# p07_cpu_renesas_144.net
KiCad netlist of a schematic drawn in Altium Designer
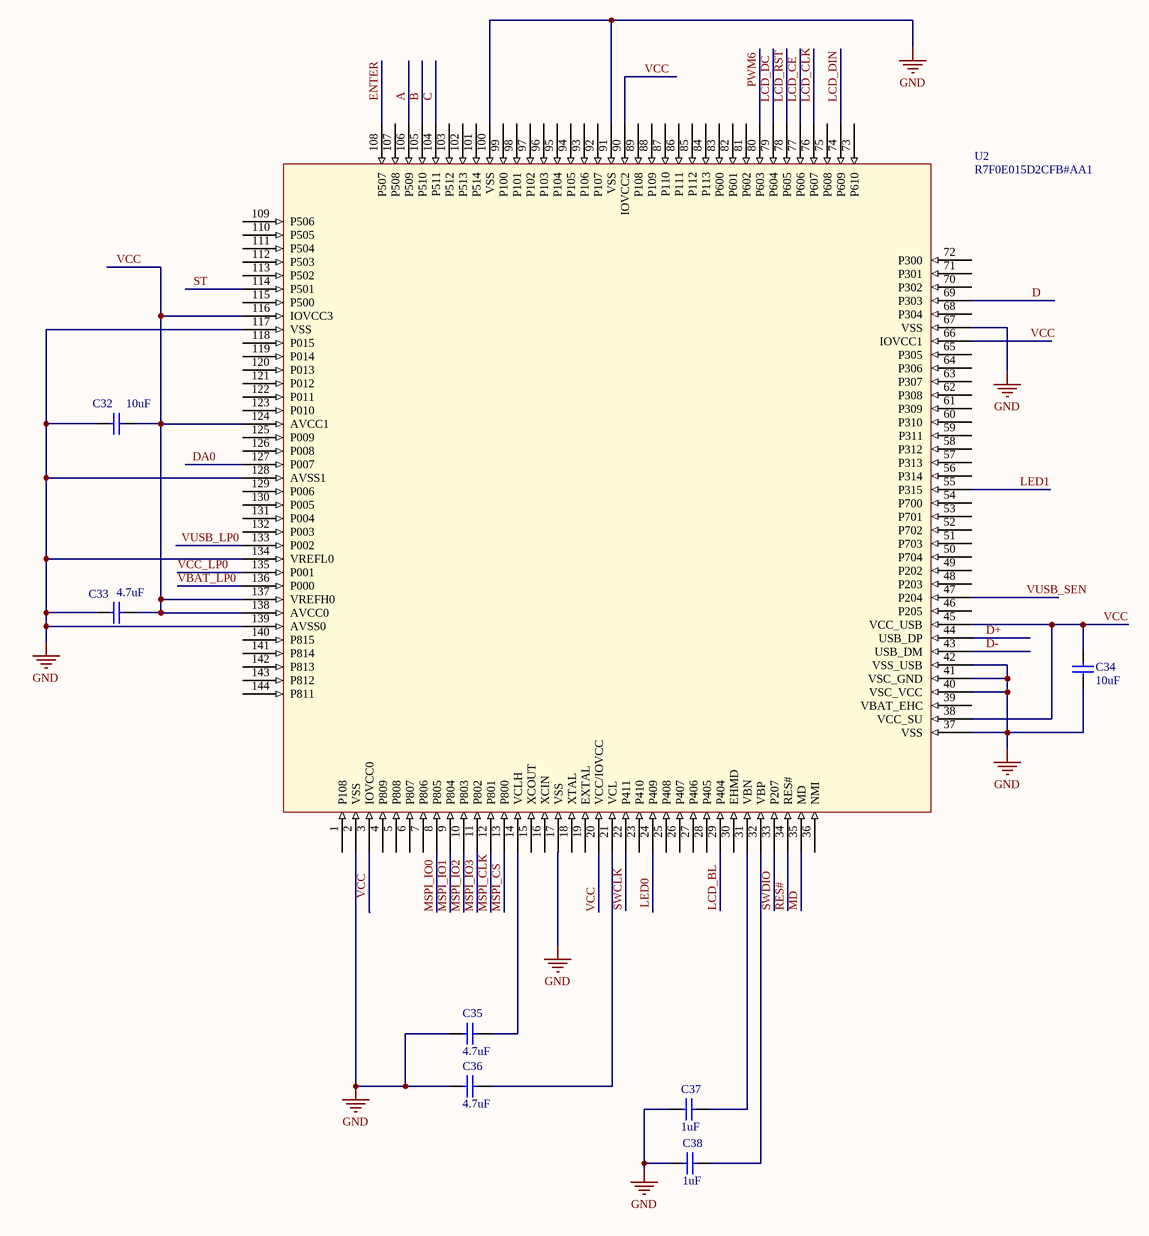
[diagram p0: p07_cpu_renesas_144.SchDoc]

(export (version "E")
  (design (tool "Eeschema 10.0.6"))
  (components
    (comp (ref "C32")
      (value "10uF")
      (footprint "Miscellaneous Devices:C1206")
      (description "Capacitor")
      (fields (field (name "Comment") "Cap") (field (name "PUBLISHER") "Altium Limited"))
      (libsource (lib "Miscellaneous Devices") (part "Cap"))
    )
    (comp (ref "C33")
      (value "4.7uF")
      (footprint "Miscellaneous Devices:C1206")
      (description "Capacitor")
      (fields (field (name "Comment") "Cap") (field (name "PUBLISHER") "Altium Limited"))
      (libsource (lib "Miscellaneous Devices") (part "Cap"))
    )
    (comp (ref "C34")
      (value "10uF")
      (footprint "Miscellaneous Devices:C1206")
      (description "Capacitor")
      (fields (field (name "Comment") "Cap") (field (name "PUBLISHER") "Altium Limited"))
      (libsource (lib "Miscellaneous Devices") (part "Cap"))
    )
    (comp (ref "C35")
      (value "4.7uF")
      (footprint "Miscellaneous Devices:C1206")
      (description "Capacitor")
      (fields (field (name "Comment") "Cap") (field (name "PUBLISHER") "Altium Limited"))
      (libsource (lib "Miscellaneous Devices") (part "Cap"))
    )
    (comp (ref "C36")
      (value "4.7uF")
      (footprint "Miscellaneous Devices:C1206")
      (description "Capacitor")
      (fields (field (name "Comment") "Cap") (field (name "PUBLISHER") "Altium Limited"))
      (libsource (lib "Miscellaneous Devices") (part "Cap"))
    )
    (comp (ref "C37")
      (value "1uF")
      (footprint "Miscellaneous Devices:C0805")
      (description "Capacitor")
      (fields (field (name "Comment") "Cap") (field (name "PUBLISHER") "Altium Limited"))
      (libsource (lib "Miscellaneous Devices") (part "Cap"))
    )
    (comp (ref "C38")
      (value "1uF")
      (footprint "Miscellaneous Devices:C0805")
      (description "Capacitor")
      (fields (field (name "Comment") "Cap") (field (name "PUBLISHER") "Altium Limited"))
      (libsource (lib "Miscellaneous Devices") (part "Cap"))
    )
    (comp (ref "U2")
      (value "R7F0E015D2CFB#AA1")
      (footprint "SQFP50P2200X2200X170-144N")
      (description "ARM® Cortex®-M0+ series Microcontroller IC 32-Bit 24MHz 1.5MB (1.5M x 8) FLASH 144-LFQFP (20x20)")
      (libsource (lib "YamagotchiLib") (part "R7F0E015D2CFB#AA1"))
    )
  )
  (nets
    (net (code "1") (name "/A") (class "Default")
      (node (ref "U2") (pin "106") (pinfunction "P509_106") (pintype "input"))
    )
    (net (code "2") (name "/B") (class "Default")
      (node (ref "U2") (pin "105") (pinfunction "P510_105") (pintype "input"))
    )
    (net (code "3") (name "/C") (class "Default")
      (node (ref "U2") (pin "104") (pinfunction "P511_104") (pintype "input"))
    )
    (net (code "4") (name "/D") (class "Default")
      (node (ref "U2") (pin "69") (pinfunction "P303_69") (pintype "input"))
    )
    (net (code "5") (name "/D+") (class "Default")
      (node (ref "U2") (pin "44") (pinfunction "USB_DP_44") (pintype "input"))
    )
    (net (code "6") (name "/D-") (class "Default")
      (node (ref "U2") (pin "43") (pinfunction "USB_DM_43") (pintype "input"))
    )
    (net (code "7") (name "/DA0") (class "Default")
      (node (ref "U2") (pin "127") (pinfunction "P007_127") (pintype "input"))
    )
    (net (code "8") (name "/ENTER") (class "Default")
      (node (ref "U2") (pin "108") (pinfunction "P507_108") (pintype "input"))
    )
    (net (code "9") (name "/LCD_BL") (class "Default")
      (node (ref "U2") (pin "29") (pinfunction "P404_29") (pintype "input"))
    )
    (net (code "10") (name "/LCD_CE") (class "Default")
      (node (ref "U2") (pin "77") (pinfunction "P606_77") (pintype "input"))
    )
    (net (code "11") (name "/LCD_CLK") (class "Default")
      (node (ref "U2") (pin "76") (pinfunction "P607_76") (pintype "input"))
    )
    (net (code "12") (name "/LCD_DC") (class "Default")
      (node (ref "U2") (pin "79") (pinfunction "P604_79") (pintype "input"))
    )
    (net (code "13") (name "/LCD_DIN") (class "Default")
      (node (ref "U2") (pin "74") (pinfunction "P609_74") (pintype "input"))
    )
    (net (code "14") (name "/LCD_RST") (class "Default")
      (node (ref "U2") (pin "78") (pinfunction "P605_78") (pintype "input"))
    )
    (net (code "15") (name "/LED0") (class "Default")
      (node (ref "U2") (pin "24") (pinfunction "P409_24") (pintype "input"))
    )
    (net (code "16") (name "/LED1") (class "Default")
      (node (ref "U2") (pin "55") (pinfunction "P315_55") (pintype "input"))
    )
    (net (code "17") (name "/MD") (class "Default")
      (node (ref "U2") (pin "35") (pinfunction "MD_35") (pintype "input"))
    )
    (net (code "18") (name "/MSPI_CLK") (class "Default")
      (node (ref "U2") (pin "12") (pinfunction "P801_12") (pintype "input"))
    )
    (net (code "19") (name "/MSPI_CS") (class "Default")
      (node (ref "U2") (pin "13") (pinfunction "P800_13") (pintype "input"))
    )
    (net (code "20") (name "/MSPI_IO0") (class "Default")
      (node (ref "U2") (pin "8") (pinfunction "P805_8") (pintype "input"))
    )
    (net (code "21") (name "/MSPI_IO1") (class "Default")
      (node (ref "U2") (pin "9") (pinfunction "P804_9") (pintype "input"))
    )
    (net (code "22") (name "/MSPI_IO2") (class "Default")
      (node (ref "U2") (pin "10") (pinfunction "P803_10") (pintype "input"))
    )
    (net (code "23") (name "/MSPI_IO3") (class "Default")
      (node (ref "U2") (pin "11") (pinfunction "P802_11") (pintype "input"))
    )
    (net (code "24") (name "/PWM6") (class "Default")
      (node (ref "U2") (pin "80") (pinfunction "P603_80") (pintype "input"))
    )
    (net (code "25") (name "/RES#") (class "Default")
      (node (ref "U2") (pin "34") (pinfunction "RES#_34") (pintype "input"))
    )
    (net (code "26") (name "/ST") (class "Default")
      (node (ref "U2") (pin "114") (pinfunction "P501_114") (pintype "input"))
    )
    (net (code "27") (name "/SWCLK") (class "Default")
      (node (ref "U2") (pin "22") (pinfunction "P411_22") (pintype "input"))
    )
    (net (code "28") (name "/SWDIO") (class "Default")
      (node (ref "U2") (pin "33") (pinfunction "P207_33") (pintype "input"))
    )
    (net (code "29") (name "/VBAT_LP0") (class "Default")
      (node (ref "U2") (pin "136") (pinfunction "P000_136") (pintype "input"))
    )
    (net (code "30") (name "/VCC") (class "Default")
      (node (ref "C32") (pin "1") (pinfunction "1_1") (pintype "passive"))
      (node (ref "C33") (pin "1") (pinfunction "1_1") (pintype "passive"))
      (node (ref "C34") (pin "2") (pinfunction "2_2") (pintype "passive"))
      (node (ref "U2") (pin "116") (pinfunction "IOVCC3_116") (pintype "input"))
      (node (ref "U2") (pin "124") (pinfunction "AVCC1_124") (pintype "input"))
      (node (ref "U2") (pin "137") (pinfunction "VREFH0_137") (pintype "input"))
      (node (ref "U2") (pin "138") (pinfunction "AVCC0_138") (pintype "input"))
      (node (ref "U2") (pin "20") (pinfunction "VCC/IOVCC_20") (pintype "input"))
      (node (ref "U2") (pin "3") (pinfunction "IOVCC0_3") (pintype "input"))
      (node (ref "U2") (pin "38") (pinfunction "VCC_SU_38") (pintype "input"))
      (node (ref "U2") (pin "45") (pinfunction "VCC_USB_45") (pintype "input"))
      (node (ref "U2") (pin "66") (pinfunction "IOVCC1_66") (pintype "input"))
      (node (ref "U2") (pin "90") (pinfunction "IOVCC2_90") (pintype "input"))
    )
    (net (code "31") (name "/VCC_LP0") (class "Default")
      (node (ref "U2") (pin "135") (pinfunction "P001_135") (pintype "input"))
    )
    (net (code "32") (name "/VUSB_LP0") (class "Default")
      (node (ref "U2") (pin "133") (pinfunction "P002_133") (pintype "input"))
    )
    (net (code "33") (name "/VUSB_SEN") (class "Default")
      (node (ref "U2") (pin "47") (pinfunction "P204_47") (pintype "input"))
    )
    (net (code "34") (name "GND") (class "Default")
      (node (ref "C32") (pin "2") (pinfunction "2_2") (pintype "passive"))
      (node (ref "C33") (pin "2") (pinfunction "2_2") (pintype "passive"))
      (node (ref "C34") (pin "1") (pinfunction "1_1") (pintype "passive"))
      (node (ref "C35") (pin "2") (pinfunction "2_2") (pintype "passive"))
      (node (ref "C36") (pin "2") (pinfunction "2_2") (pintype "passive"))
      (node (ref "C37") (pin "1") (pinfunction "1_1") (pintype "passive"))
      (node (ref "C38") (pin "1") (pinfunction "1_1") (pintype "passive"))
      (node (ref "U2") (pin "100") (pinfunction "VSS_100") (pintype "input"))
      (node (ref "U2") (pin "117") (pinfunction "VSS_117") (pintype "input"))
      (node (ref "U2") (pin "128") (pinfunction "AVSS1_128") (pintype "input"))
      (node (ref "U2") (pin "134") (pinfunction "VREFL0_134") (pintype "input"))
      (node (ref "U2") (pin "139") (pinfunction "AVSS0_139") (pintype "input"))
      (node (ref "U2") (pin "17") (pinfunction "VSS_17") (pintype "input"))
      (node (ref "U2") (pin "2") (pinfunction "VSS_2") (pintype "input"))
      (node (ref "U2") (pin "37") (pinfunction "VSS_37") (pintype "input"))
      (node (ref "U2") (pin "40") (pinfunction "VSC_VCC_40") (pintype "input"))
      (node (ref "U2") (pin "41") (pinfunction "VSC_GND_41") (pintype "input"))
      (node (ref "U2") (pin "42") (pinfunction "VSS_USB_42") (pintype "input"))
      (node (ref "U2") (pin "67") (pinfunction "VSS_67") (pintype "input"))
      (node (ref "U2") (pin "91") (pinfunction "VSS_91") (pintype "input"))
    )
    (net (code "35") (name "Net-(U2-VBN)") (class "Default")
      (node (ref "C37") (pin "2") (pinfunction "2_2") (pintype "passive"))
      (node (ref "U2") (pin "31") (pinfunction "VBN_31") (pintype "input"))
    )
    (net (code "36") (name "Net-(U2-VBP)") (class "Default")
      (node (ref "C38") (pin "2") (pinfunction "2_2") (pintype "passive"))
      (node (ref "U2") (pin "32") (pinfunction "VBP_32") (pintype "input"))
    )
    (net (code "37") (name "Net-(U2-VCL)") (class "Default")
      (node (ref "C36") (pin "1") (pinfunction "1_1") (pintype "passive"))
      (node (ref "U2") (pin "21") (pinfunction "VCL_21") (pintype "input"))
    )
    (net (code "38") (name "Net-(U2-VCLH)") (class "Default")
      (node (ref "C35") (pin "1") (pinfunction "1_1") (pintype "passive"))
      (node (ref "U2") (pin "14") (pinfunction "VCLH_14") (pintype "input"))
    )
    (net (code "39") (name "unconnected-(U2-EHMD-Pad30)") (class "Default")
      (node (ref "U2") (pin "30") (pinfunction "EHMD_30") (pintype "input"))
    )
    (net (code "40") (name "unconnected-(U2-EXTAL-Pad19)") (class "Default")
      (node (ref "U2") (pin "19") (pinfunction "EXTAL_19") (pintype "input"))
    )
    (net (code "41") (name "unconnected-(U2-NMI-Pad36)") (class "Default")
      (node (ref "U2") (pin "36") (pinfunction "NMI_36") (pintype "input"))
    )
    (net (code "42") (name "unconnected-(U2-P003-Pad132)") (class "Default")
      (node (ref "U2") (pin "132") (pinfunction "P003_132") (pintype "input"))
    )
    (net (code "43") (name "unconnected-(U2-P004-Pad131)") (class "Default")
      (node (ref "U2") (pin "131") (pinfunction "P004_131") (pintype "input"))
    )
    (net (code "44") (name "unconnected-(U2-P005-Pad130)") (class "Default")
      (node (ref "U2") (pin "130") (pinfunction "P005_130") (pintype "input"))
    )
    (net (code "45") (name "unconnected-(U2-P006-Pad129)") (class "Default")
      (node (ref "U2") (pin "129") (pinfunction "P006_129") (pintype "input"))
    )
    (net (code "46") (name "unconnected-(U2-P008-Pad126)") (class "Default")
      (node (ref "U2") (pin "126") (pinfunction "P008_126") (pintype "input"))
    )
    (net (code "47") (name "unconnected-(U2-P009-Pad125)") (class "Default")
      (node (ref "U2") (pin "125") (pinfunction "P009_125") (pintype "input"))
    )
    (net (code "48") (name "unconnected-(U2-P010-Pad123)") (class "Default")
      (node (ref "U2") (pin "123") (pinfunction "P010_123") (pintype "input"))
    )
    (net (code "49") (name "unconnected-(U2-P011-Pad122)") (class "Default")
      (node (ref "U2") (pin "122") (pinfunction "P011_122") (pintype "input"))
    )
    (net (code "50") (name "unconnected-(U2-P012-Pad121)") (class "Default")
      (node (ref "U2") (pin "121") (pinfunction "P012_121") (pintype "input"))
    )
    (net (code "51") (name "unconnected-(U2-P013-Pad120)") (class "Default")
      (node (ref "U2") (pin "120") (pinfunction "P013_120") (pintype "input"))
    )
    (net (code "52") (name "unconnected-(U2-P014-Pad119)") (class "Default")
      (node (ref "U2") (pin "119") (pinfunction "P014_119") (pintype "input"))
    )
    (net (code "53") (name "unconnected-(U2-P015-Pad118)") (class "Default")
      (node (ref "U2") (pin "118") (pinfunction "P015_118") (pintype "input"))
    )
    (net (code "54") (name "unconnected-(U2-P100-Pad99)") (class "Default")
      (node (ref "U2") (pin "99") (pinfunction "P100_99") (pintype "input"))
    )
    (net (code "55") (name "unconnected-(U2-P101-Pad98)") (class "Default")
      (node (ref "U2") (pin "98") (pinfunction "P101_98") (pintype "input"))
    )
    (net (code "56") (name "unconnected-(U2-P102-Pad97)") (class "Default")
      (node (ref "U2") (pin "97") (pinfunction "P102_97") (pintype "input"))
    )
    (net (code "57") (name "unconnected-(U2-P103-Pad96)") (class "Default")
      (node (ref "U2") (pin "96") (pinfunction "P103_96") (pintype "input"))
    )
    (net (code "58") (name "unconnected-(U2-P104-Pad95)") (class "Default")
      (node (ref "U2") (pin "95") (pinfunction "P104_95") (pintype "input"))
    )
    (net (code "59") (name "unconnected-(U2-P105-Pad94)") (class "Default")
      (node (ref "U2") (pin "94") (pinfunction "P105_94") (pintype "input"))
    )
    (net (code "60") (name "unconnected-(U2-P106-Pad93)") (class "Default")
      (node (ref "U2") (pin "93") (pinfunction "P106_93") (pintype "input"))
    )
    (net (code "61") (name "unconnected-(U2-P107-Pad92)") (class "Default")
      (node (ref "U2") (pin "92") (pinfunction "P107_92") (pintype "input"))
    )
    (net (code "62") (name "unconnected-(U2-P108-Pad1)") (class "Default")
      (node (ref "U2") (pin "1") (pinfunction "P108_1") (pintype "input"))
    )
    (net (code "63") (name "unconnected-(U2-P108-Pad89)") (class "Default")
      (node (ref "U2") (pin "89") (pinfunction "P108_89") (pintype "input"))
    )
    (net (code "64") (name "unconnected-(U2-P109-Pad88)") (class "Default")
      (node (ref "U2") (pin "88") (pinfunction "P109_88") (pintype "input"))
    )
    (net (code "65") (name "unconnected-(U2-P110-Pad87)") (class "Default")
      (node (ref "U2") (pin "87") (pinfunction "P110_87") (pintype "input"))
    )
    (net (code "66") (name "unconnected-(U2-P111-Pad86)") (class "Default")
      (node (ref "U2") (pin "86") (pinfunction "P111_86") (pintype "input"))
    )
    (net (code "67") (name "unconnected-(U2-P112-Pad85)") (class "Default")
      (node (ref "U2") (pin "85") (pinfunction "P112_85") (pintype "input"))
    )
    (net (code "68") (name "unconnected-(U2-P113-Pad84)") (class "Default")
      (node (ref "U2") (pin "84") (pinfunction "P113_84") (pintype "input"))
    )
    (net (code "69") (name "unconnected-(U2-P202-Pad49)") (class "Default")
      (node (ref "U2") (pin "49") (pinfunction "P202_49") (pintype "input"))
    )
    (net (code "70") (name "unconnected-(U2-P203-Pad48)") (class "Default")
      (node (ref "U2") (pin "48") (pinfunction "P203_48") (pintype "input"))
    )
    (net (code "71") (name "unconnected-(U2-P205-Pad46)") (class "Default")
      (node (ref "U2") (pin "46") (pinfunction "P205_46") (pintype "input"))
    )
    (net (code "72") (name "unconnected-(U2-P300-Pad72)") (class "Default")
      (node (ref "U2") (pin "72") (pinfunction "P300_72") (pintype "input"))
    )
    (net (code "73") (name "unconnected-(U2-P301-Pad71)") (class "Default")
      (node (ref "U2") (pin "71") (pinfunction "P301_71") (pintype "input"))
    )
    (net (code "74") (name "unconnected-(U2-P302-Pad70)") (class "Default")
      (node (ref "U2") (pin "70") (pinfunction "P302_70") (pintype "input"))
    )
    (net (code "75") (name "unconnected-(U2-P304-Pad68)") (class "Default")
      (node (ref "U2") (pin "68") (pinfunction "P304_68") (pintype "input"))
    )
    (net (code "76") (name "unconnected-(U2-P305-Pad65)") (class "Default")
      (node (ref "U2") (pin "65") (pinfunction "P305_65") (pintype "input"))
    )
    (net (code "77") (name "unconnected-(U2-P306-Pad64)") (class "Default")
      (node (ref "U2") (pin "64") (pinfunction "P306_64") (pintype "input"))
    )
    (net (code "78") (name "unconnected-(U2-P307-Pad63)") (class "Default")
      (node (ref "U2") (pin "63") (pinfunction "P307_63") (pintype "input"))
    )
    (net (code "79") (name "unconnected-(U2-P308-Pad62)") (class "Default")
      (node (ref "U2") (pin "62") (pinfunction "P308_62") (pintype "input"))
    )
    (net (code "80") (name "unconnected-(U2-P309-Pad61)") (class "Default")
      (node (ref "U2") (pin "61") (pinfunction "P309_61") (pintype "input"))
    )
    (net (code "81") (name "unconnected-(U2-P310-Pad60)") (class "Default")
      (node (ref "U2") (pin "60") (pinfunction "P310_60") (pintype "input"))
    )
    (net (code "82") (name "unconnected-(U2-P311-Pad59)") (class "Default")
      (node (ref "U2") (pin "59") (pinfunction "P311_59") (pintype "input"))
    )
    (net (code "83") (name "unconnected-(U2-P312-Pad58)") (class "Default")
      (node (ref "U2") (pin "58") (pinfunction "P312_58") (pintype "input"))
    )
    (net (code "84") (name "unconnected-(U2-P313-Pad57)") (class "Default")
      (node (ref "U2") (pin "57") (pinfunction "P313_57") (pintype "input"))
    )
    (net (code "85") (name "unconnected-(U2-P314-Pad56)") (class "Default")
      (node (ref "U2") (pin "56") (pinfunction "P314_56") (pintype "input"))
    )
    (net (code "86") (name "unconnected-(U2-P405-Pad28)") (class "Default")
      (node (ref "U2") (pin "28") (pinfunction "P405_28") (pintype "input"))
    )
    (net (code "87") (name "unconnected-(U2-P406-Pad27)") (class "Default")
      (node (ref "U2") (pin "27") (pinfunction "P406_27") (pintype "input"))
    )
    (net (code "88") (name "unconnected-(U2-P407-Pad26)") (class "Default")
      (node (ref "U2") (pin "26") (pinfunction "P407_26") (pintype "input"))
    )
    (net (code "89") (name "unconnected-(U2-P408-Pad25)") (class "Default")
      (node (ref "U2") (pin "25") (pinfunction "P408_25") (pintype "input"))
    )
    (net (code "90") (name "unconnected-(U2-P410-Pad23)") (class "Default")
      (node (ref "U2") (pin "23") (pinfunction "P410_23") (pintype "input"))
    )
    (net (code "91") (name "unconnected-(U2-P500-Pad115)") (class "Default")
      (node (ref "U2") (pin "115") (pinfunction "P500_115") (pintype "input"))
    )
    (net (code "92") (name "unconnected-(U2-P502-Pad113)") (class "Default")
      (node (ref "U2") (pin "113") (pinfunction "P502_113") (pintype "input"))
    )
    (net (code "93") (name "unconnected-(U2-P503-Pad112)") (class "Default")
      (node (ref "U2") (pin "112") (pinfunction "P503_112") (pintype "input"))
    )
    (net (code "94") (name "unconnected-(U2-P504-Pad111)") (class "Default")
      (node (ref "U2") (pin "111") (pinfunction "P504_111") (pintype "input"))
    )
    (net (code "95") (name "unconnected-(U2-P505-Pad110)") (class "Default")
      (node (ref "U2") (pin "110") (pinfunction "P505_110") (pintype "input"))
    )
    (net (code "96") (name "unconnected-(U2-P506-Pad109)") (class "Default")
      (node (ref "U2") (pin "109") (pinfunction "P506_109") (pintype "input"))
    )
    (net (code "97") (name "unconnected-(U2-P508-Pad107)") (class "Default")
      (node (ref "U2") (pin "107") (pinfunction "P508_107") (pintype "input"))
    )
    (net (code "98") (name "unconnected-(U2-P512-Pad103)") (class "Default")
      (node (ref "U2") (pin "103") (pinfunction "P512_103") (pintype "input"))
    )
    (net (code "99") (name "unconnected-(U2-P513-Pad102)") (class "Default")
      (node (ref "U2") (pin "102") (pinfunction "P513_102") (pintype "input"))
    )
    (net (code "100") (name "unconnected-(U2-P514-Pad101)") (class "Default")
      (node (ref "U2") (pin "101") (pinfunction "P514_101") (pintype "input"))
    )
    (net (code "101") (name "unconnected-(U2-P600-Pad83)") (class "Default")
      (node (ref "U2") (pin "83") (pinfunction "P600_83") (pintype "input"))
    )
    (net (code "102") (name "unconnected-(U2-P601-Pad82)") (class "Default")
      (node (ref "U2") (pin "82") (pinfunction "P601_82") (pintype "input"))
    )
    (net (code "103") (name "unconnected-(U2-P602-Pad81)") (class "Default")
      (node (ref "U2") (pin "81") (pinfunction "P602_81") (pintype "input"))
    )
    (net (code "104") (name "unconnected-(U2-P608-Pad75)") (class "Default")
      (node (ref "U2") (pin "75") (pinfunction "P608_75") (pintype "input"))
    )
    (net (code "105") (name "unconnected-(U2-P610-Pad73)") (class "Default")
      (node (ref "U2") (pin "73") (pinfunction "P610_73") (pintype "input"))
    )
    (net (code "106") (name "unconnected-(U2-P700-Pad54)") (class "Default")
      (node (ref "U2") (pin "54") (pinfunction "P700_54") (pintype "input"))
    )
    (net (code "107") (name "unconnected-(U2-P701-Pad53)") (class "Default")
      (node (ref "U2") (pin "53") (pinfunction "P701_53") (pintype "input"))
    )
    (net (code "108") (name "unconnected-(U2-P702-Pad52)") (class "Default")
      (node (ref "U2") (pin "52") (pinfunction "P702_52") (pintype "input"))
    )
    (net (code "109") (name "unconnected-(U2-P703-Pad51)") (class "Default")
      (node (ref "U2") (pin "51") (pinfunction "P703_51") (pintype "input"))
    )
    (net (code "110") (name "unconnected-(U2-P704-Pad50)") (class "Default")
      (node (ref "U2") (pin "50") (pinfunction "P704_50") (pintype "input"))
    )
    (net (code "111") (name "unconnected-(U2-P806-Pad7)") (class "Default")
      (node (ref "U2") (pin "7") (pinfunction "P806_7") (pintype "input"))
    )
    (net (code "112") (name "unconnected-(U2-P807-Pad6)") (class "Default")
      (node (ref "U2") (pin "6") (pinfunction "P807_6") (pintype "input"))
    )
    (net (code "113") (name "unconnected-(U2-P808-Pad5)") (class "Default")
      (node (ref "U2") (pin "5") (pinfunction "P808_5") (pintype "input"))
    )
    (net (code "114") (name "unconnected-(U2-P809-Pad4)") (class "Default")
      (node (ref "U2") (pin "4") (pinfunction "P809_4") (pintype "input"))
    )
    (net (code "115") (name "unconnected-(U2-P811-Pad144)") (class "Default")
      (node (ref "U2") (pin "144") (pinfunction "P811_144") (pintype "input"))
    )
    (net (code "116") (name "unconnected-(U2-P812-Pad143)") (class "Default")
      (node (ref "U2") (pin "143") (pinfunction "P812_143") (pintype "input"))
    )
    (net (code "117") (name "unconnected-(U2-P813-Pad142)") (class "Default")
      (node (ref "U2") (pin "142") (pinfunction "P813_142") (pintype "input"))
    )
    (net (code "118") (name "unconnected-(U2-P814-Pad141)") (class "Default")
      (node (ref "U2") (pin "141") (pinfunction "P814_141") (pintype "input"))
    )
    (net (code "119") (name "unconnected-(U2-P815-Pad140)") (class "Default")
      (node (ref "U2") (pin "140") (pinfunction "P815_140") (pintype "input"))
    )
    (net (code "120") (name "unconnected-(U2-VBAT_EHC-Pad39)") (class "Default")
      (node (ref "U2") (pin "39") (pinfunction "VBAT_EHC_39") (pintype "input"))
    )
    (net (code "121") (name "unconnected-(U2-XCIN-Pad16)") (class "Default")
      (node (ref "U2") (pin "16") (pinfunction "XCIN_16") (pintype "input"))
    )
    (net (code "122") (name "unconnected-(U2-XCOUT-Pad15)") (class "Default")
      (node (ref "U2") (pin "15") (pinfunction "XCOUT_15") (pintype "input"))
    )
    (net (code "123") (name "unconnected-(U2-XTAL-Pad18)") (class "Default")
      (node (ref "U2") (pin "18") (pinfunction "XTAL_18") (pintype "input"))
    )
  )
)
